# Motor.net
KiCad netlist of a schematic drawn in Altium Designer
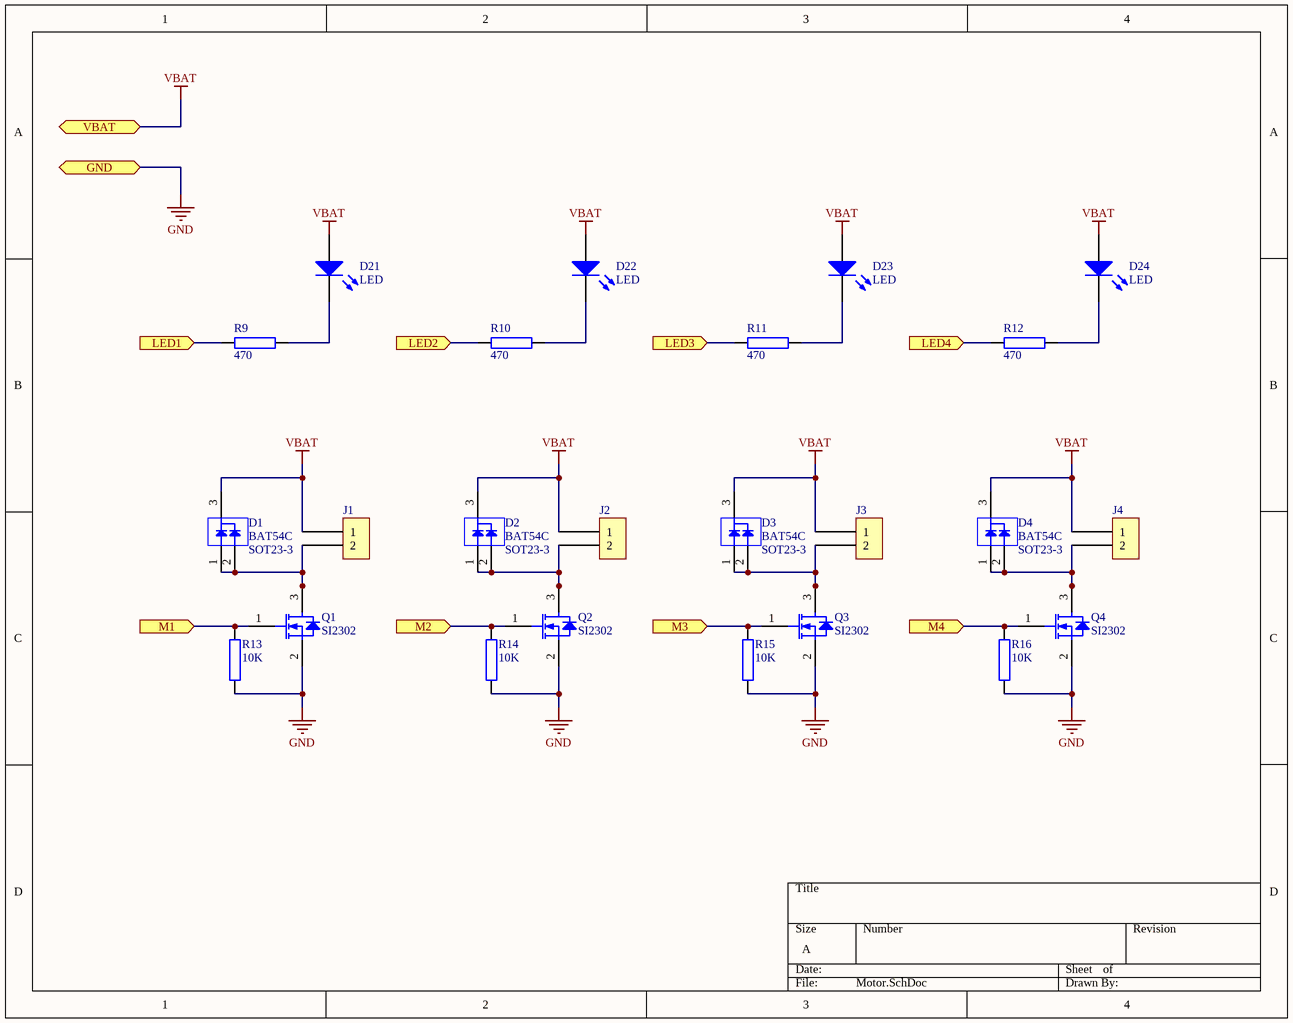
[diagram p0: Motor.SchDoc]

(export (version "E")
  (design (tool "Eeschema 10.0.6"))
  (components
    (comp (ref "D1") (value "BAT54C") (footprint "SOT23-3") (libsource (lib "Quadcopter") (part "BAT54C")))
    (comp (ref "D2") (value "BAT54C") (footprint "SOT23-3") (libsource (lib "Quadcopter") (part "BAT54C")))
    (comp (ref "D3") (value "BAT54C") (footprint "SOT23-3") (libsource (lib "Quadcopter") (part "BAT54C")))
    (comp (ref "D4") (value "BAT54C") (footprint "SOT23-3") (libsource (lib "Quadcopter") (part "BAT54C")))
    (comp (ref "D21")
      (value "LED")
      (footprint "LED_0603")
      (description "Typical INFRARED GaAs LED")
      (fields (field (name "PUBLISHER") "Altium Limited"))
      (libsource (lib "Quadcopter") (part "LED"))
    )
    (comp (ref "D22")
      (value "LED")
      (footprint "LED_0603")
      (description "Typical INFRARED GaAs LED")
      (fields (field (name "PUBLISHER") "Altium Limited"))
      (libsource (lib "Quadcopter") (part "LED"))
    )
    (comp (ref "D23")
      (value "LED")
      (footprint "LED_0603")
      (description "Typical INFRARED GaAs LED")
      (fields (field (name "PUBLISHER") "Altium Limited"))
      (libsource (lib "Quadcopter") (part "LED"))
    )
    (comp (ref "D24")
      (value "LED")
      (footprint "LED_0603")
      (description "Typical INFRARED GaAs LED")
      (fields (field (name "PUBLISHER") "Altium Limited"))
      (libsource (lib "Quadcopter") (part "LED"))
    )
    (comp (ref "J1")
      (value "motor bonding pad")
      (footprint "Motor_Pin_Pad")
      (libsource (lib "Quadcopter") (part "Joint_Motor"))
    )
    (comp (ref "J2")
      (value "motor bonding pad")
      (footprint "Motor_Pin_Pad")
      (libsource (lib "Quadcopter") (part "Joint_Motor"))
    )
    (comp (ref "J3")
      (value "motor bonding pad")
      (footprint "Motor_Pin_Pad")
      (libsource (lib "Quadcopter") (part "Joint_Motor"))
    )
    (comp (ref "J4")
      (value "motor bonding pad")
      (footprint "Motor_Pin_Pad")
      (libsource (lib "Quadcopter") (part "Joint_Motor"))
    )
    (comp (ref "Q1")
      (value "SI2302")
      (footprint "SOT23-3")
      (description "N-Channel MOSFET")
      (fields (field (name "PUBLISHER") "Altium Limited"))
      (libsource (lib "Quadcopter") (part "SI2302"))
    )
    (comp (ref "Q2")
      (value "SI2302")
      (footprint "SOT23-3")
      (description "N-Channel MOSFET")
      (fields (field (name "PUBLISHER") "Altium Limited"))
      (libsource (lib "Quadcopter") (part "SI2302"))
    )
    (comp (ref "Q3")
      (value "SI2302")
      (footprint "SOT23-3")
      (description "N-Channel MOSFET")
      (fields (field (name "PUBLISHER") "Altium Limited"))
      (libsource (lib "Quadcopter") (part "SI2302"))
    )
    (comp (ref "Q4")
      (value "SI2302")
      (footprint "SOT23-3")
      (description "N-Channel MOSFET")
      (fields (field (name "PUBLISHER") "Altium Limited"))
      (libsource (lib "Quadcopter") (part "SI2302"))
    )
    (comp (ref "R9")
      (value "470")
      (footprint "R0603")
      (description "Resistor")
      (fields (field (name "PUBLISHER") "Altium Limited"))
      (libsource (lib "Quadcopter") (part "Res3"))
    )
    (comp (ref "R10")
      (value "470")
      (footprint "R0603")
      (description "Resistor")
      (fields (field (name "PUBLISHER") "Altium Limited"))
      (libsource (lib "Quadcopter") (part "Res3"))
    )
    (comp (ref "R11")
      (value "470")
      (footprint "R0603")
      (description "Resistor")
      (fields (field (name "PUBLISHER") "Altium Limited"))
      (libsource (lib "Quadcopter") (part "Res3"))
    )
    (comp (ref "R12")
      (value "470")
      (footprint "R0603")
      (description "Resistor")
      (fields (field (name "PUBLISHER") "Altium Limited"))
      (libsource (lib "Quadcopter") (part "Res3"))
    )
    (comp (ref "R13")
      (value "10K")
      (footprint "R0603")
      (description "Resistor")
      (fields (field (name "PUBLISHER") "Altium Limited"))
      (libsource (lib "Quadcopter") (part "Res3"))
    )
    (comp (ref "R14")
      (value "10K")
      (footprint "R0603")
      (description "Resistor")
      (fields (field (name "PUBLISHER") "Altium Limited"))
      (libsource (lib "Quadcopter") (part "Res3"))
    )
    (comp (ref "R15")
      (value "10K")
      (footprint "R0603")
      (description "Resistor")
      (fields (field (name "PUBLISHER") "Altium Limited"))
      (libsource (lib "Quadcopter") (part "Res3"))
    )
    (comp (ref "R16")
      (value "10K")
      (footprint "R0603")
      (description "Resistor")
      (fields (field (name "PUBLISHER") "Altium Limited"))
      (libsource (lib "Quadcopter") (part "Res3"))
    )
  )
  (nets
    (net (code "1") (name "/LED1") (class "Default")
      (node (ref "R9") (pin "1") (pinfunction "1_1") (pintype "passive"))
    )
    (net (code "2") (name "/LED2") (class "Default")
      (node (ref "R10") (pin "1") (pinfunction "1_1") (pintype "passive"))
    )
    (net (code "3") (name "/LED3") (class "Default")
      (node (ref "R11") (pin "1") (pinfunction "1_1") (pintype "passive"))
    )
    (net (code "4") (name "/LED4") (class "Default")
      (node (ref "R12") (pin "1") (pinfunction "1_1") (pintype "passive"))
    )
    (net (code "5") (name "/M1") (class "Default")
      (node (ref "Q1") (pin "1") (pinfunction "G_1") (pintype "passive"))
      (node (ref "R13") (pin "2") (pinfunction "2_2") (pintype "passive"))
    )
    (net (code "6") (name "/M2") (class "Default")
      (node (ref "Q2") (pin "1") (pinfunction "G_1") (pintype "passive"))
      (node (ref "R14") (pin "2") (pinfunction "2_2") (pintype "passive"))
    )
    (net (code "7") (name "/M3") (class "Default")
      (node (ref "Q3") (pin "1") (pinfunction "G_1") (pintype "passive"))
      (node (ref "R15") (pin "2") (pinfunction "2_2") (pintype "passive"))
    )
    (net (code "8") (name "/M4") (class "Default")
      (node (ref "Q4") (pin "1") (pinfunction "G_1") (pintype "passive"))
      (node (ref "R16") (pin "2") (pinfunction "2_2") (pintype "passive"))
    )
    (net (code "9") (name "GND") (class "Default")
      (node (ref "Q1") (pin "2") (pinfunction "S_2") (pintype "passive"))
      (node (ref "Q2") (pin "2") (pinfunction "S_2") (pintype "passive"))
      (node (ref "Q3") (pin "2") (pinfunction "S_2") (pintype "passive"))
      (node (ref "Q4") (pin "2") (pinfunction "S_2") (pintype "passive"))
      (node (ref "R13") (pin "1") (pinfunction "1_1") (pintype "passive"))
      (node (ref "R14") (pin "1") (pinfunction "1_1") (pintype "passive"))
      (node (ref "R15") (pin "1") (pinfunction "1_1") (pintype "passive"))
      (node (ref "R16") (pin "1") (pinfunction "1_1") (pintype "passive"))
    )
    (net (code "10") (name "Net-(D21-K)") (class "Default")
      (node (ref "D21") (pin "2") (pinfunction "K_2") (pintype "passive"))
      (node (ref "R9") (pin "2") (pinfunction "2_2") (pintype "passive"))
    )
    (net (code "11") (name "Net-(D22-K)") (class "Default")
      (node (ref "D22") (pin "2") (pinfunction "K_2") (pintype "passive"))
      (node (ref "R10") (pin "2") (pinfunction "2_2") (pintype "passive"))
    )
    (net (code "12") (name "Net-(D23-K)") (class "Default")
      (node (ref "D23") (pin "2") (pinfunction "K_2") (pintype "passive"))
      (node (ref "R11") (pin "2") (pinfunction "2_2") (pintype "passive"))
    )
    (net (code "13") (name "Net-(D24-K)") (class "Default")
      (node (ref "D24") (pin "2") (pinfunction "K_2") (pintype "passive"))
      (node (ref "R12") (pin "2") (pinfunction "2_2") (pintype "passive"))
    )
    (net (code "14") (name "Net-(Q1-D)") (class "Default")
      (node (ref "D1") (pin "1") (pinfunction "1_1") (pintype "passive"))
      (node (ref "D1") (pin "2") (pinfunction "2_2") (pintype "passive"))
      (node (ref "J1") (pin "2") (pinfunction "2_2") (pintype "passive"))
      (node (ref "Q1") (pin "3") (pinfunction "D_3") (pintype "passive"))
    )
    (net (code "15") (name "Net-(Q2-D)") (class "Default")
      (node (ref "D2") (pin "1") (pinfunction "1_1") (pintype "passive"))
      (node (ref "D2") (pin "2") (pinfunction "2_2") (pintype "passive"))
      (node (ref "J2") (pin "2") (pinfunction "2_2") (pintype "passive"))
      (node (ref "Q2") (pin "3") (pinfunction "D_3") (pintype "passive"))
    )
    (net (code "16") (name "Net-(Q3-D)") (class "Default")
      (node (ref "D3") (pin "1") (pinfunction "1_1") (pintype "passive"))
      (node (ref "D3") (pin "2") (pinfunction "2_2") (pintype "passive"))
      (node (ref "J3") (pin "2") (pinfunction "2_2") (pintype "passive"))
      (node (ref "Q3") (pin "3") (pinfunction "D_3") (pintype "passive"))
    )
    (net (code "17") (name "Net-(Q4-D)") (class "Default")
      (node (ref "D4") (pin "1") (pinfunction "1_1") (pintype "passive"))
      (node (ref "D4") (pin "2") (pinfunction "2_2") (pintype "passive"))
      (node (ref "J4") (pin "2") (pinfunction "2_2") (pintype "passive"))
      (node (ref "Q4") (pin "3") (pinfunction "D_3") (pintype "passive"))
    )
    (net (code "18") (name "VBAT") (class "Default")
      (node (ref "D1") (pin "3") (pinfunction "3_3") (pintype "passive"))
      (node (ref "D2") (pin "3") (pinfunction "3_3") (pintype "passive"))
      (node (ref "D21") (pin "1") (pinfunction "A_1") (pintype "passive"))
      (node (ref "D22") (pin "1") (pinfunction "A_1") (pintype "passive"))
      (node (ref "D23") (pin "1") (pinfunction "A_1") (pintype "passive"))
      (node (ref "D24") (pin "1") (pinfunction "A_1") (pintype "passive"))
      (node (ref "D3") (pin "3") (pinfunction "3_3") (pintype "passive"))
      (node (ref "D4") (pin "3") (pinfunction "3_3") (pintype "passive"))
      (node (ref "J1") (pin "1") (pinfunction "1_1") (pintype "passive"))
      (node (ref "J2") (pin "1") (pinfunction "1_1") (pintype "passive"))
      (node (ref "J3") (pin "1") (pinfunction "1_1") (pintype "passive"))
      (node (ref "J4") (pin "1") (pinfunction "1_1") (pintype "passive"))
    )
  )
)
